# ATTiny5.net
KiCad netlist of a schematic drawn in EAGLE
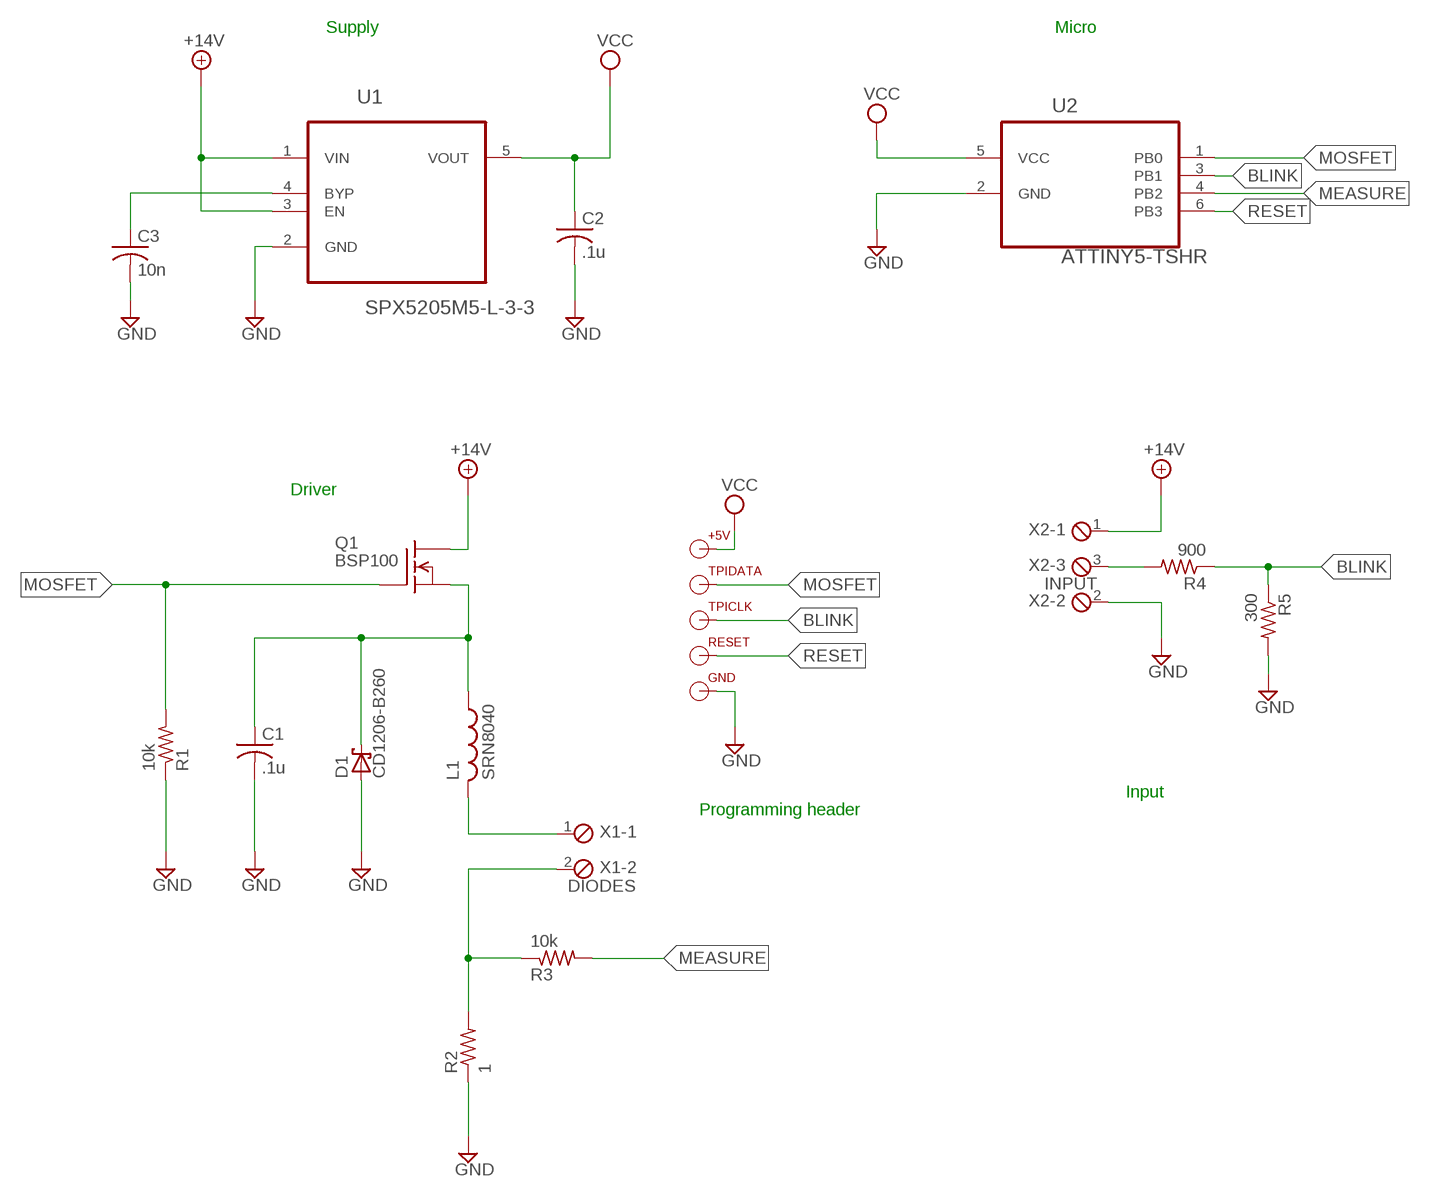
[diagram p0: schematic, sheet 1]

(export (version "E")
  (design (tool "Eeschema 10.0.6"))
  (components
    (comp (ref "+5V")
      (value "TPI")
      (footprint "eagle-import:TPI_PAD")
      (libsource (lib "eagle-import") (part "TPI"))
    )
    (comp (ref "C1")
      (value ".1u")
      (footprint "eagle-import:C0805")
      (libsource (lib "eagle-import") (part "C-USC0805"))
    )
    (comp (ref "C2")
      (value ".1u")
      (footprint "eagle-import:C0805")
      (libsource (lib "eagle-import") (part "C-USC0805"))
    )
    (comp (ref "C3")
      (value "10n")
      (footprint "eagle-import:C0603")
      (libsource (lib "eagle-import") (part "C-USC0603"))
    )
    (comp (ref "D1")
      (value "CD1206-B260")
      (footprint "eagle-import:D1206")
      (libsource (lib "eagle-import") (part "CD1206-B260"))
    )
    (comp (ref "GND")
      (value "TPI")
      (footprint "eagle-import:TPI_PAD")
      (libsource (lib "eagle-import") (part "TPI"))
    )
    (comp (ref "L1")
      (value "SRN8040")
      (footprint "eagle-import:SRN8040")
      (libsource (lib "eagle-import") (part "SRN8040"))
    )
    (comp (ref "Q1")
      (value "BSP100")
      (footprint "eagle-import:SOT223")
      (libsource (lib "eagle-import") (part "BSP100"))
    )
    (comp (ref "R1")
      (value "10k")
      (footprint "eagle-import:R1206")
      (libsource (lib "eagle-import") (part "R-US_R1206"))
    )
    (comp (ref "R2")
      (value "1")
      (footprint "eagle-import:R1206")
      (libsource (lib "eagle-import") (part "R-US_R1206"))
    )
    (comp (ref "R3")
      (value "10k")
      (footprint "eagle-import:R1206")
      (libsource (lib "eagle-import") (part "R-US_R1206"))
    )
    (comp (ref "R4")
      (value "900")
      (footprint "eagle-import:R1206")
      (libsource (lib "eagle-import") (part "R-US_R1206"))
    )
    (comp (ref "R5")
      (value "300")
      (footprint "eagle-import:R1206")
      (libsource (lib "eagle-import") (part "R-US_R1206"))
    )
    (comp (ref "RESET")
      (value "TPI")
      (footprint "eagle-import:TPI_PAD")
      (libsource (lib "eagle-import") (part "TPI"))
    )
    (comp (ref "TPICLK")
      (value "TPI")
      (footprint "eagle-import:TPI_PAD")
      (libsource (lib "eagle-import") (part "TPI"))
    )
    (comp (ref "TPIDATA")
      (value "TPI")
      (footprint "eagle-import:TPI_PAD")
      (libsource (lib "eagle-import") (part "TPI"))
    )
    (comp (ref "U1")
      (value "SPX5205M5-L-3-3")
      (footprint "eagle-import:SOT95P280X145-5N")
      (libsource (lib "eagle-import") (part "SPX5205M5-L-3-3"))
    )
    (comp (ref "U2")
      (value "ATTINY5-TSHR")
      (footprint "eagle-import:SOT95P280X145-6N")
      (libsource (lib "eagle-import") (part "ATTINY5-TSHR"))
    )
    (comp (ref "X1")
      (value "DIODES")
      (footprint "eagle-import:2POL254")
      (libsource (lib "eagle-import") (part "MPT2"))
    )
    (comp (ref "X2")
      (value "INPUT")
      (footprint "eagle-import:3POL254")
      (libsource (lib "eagle-import") (part "MPT3"))
    )
  )
  (nets
    (net (code "1") (name "+14V") (class "Default")
      (node (ref "Q1") (pin "2") (pinfunction "D_2") (pintype "passive"))
      (node (ref "Q1") (pin "TAB") (pinfunction "D_TAB") (pintype "passive"))
      (node (ref "U1") (pin "1") (pinfunction "VIN_1") (pintype "power_in"))
      (node (ref "U1") (pin "3") (pinfunction "EN_3") (pintype "input"))
      (node (ref "X2") (pin "1") (pinfunction "1_1") (pintype "passive"))
    )
    (net (code "2") (name "BLINK") (class "Default")
      (node (ref "R4") (pin "1") (pinfunction "1_1") (pintype "passive"))
      (node (ref "R5") (pin "1") (pinfunction "1_1") (pintype "passive"))
      (node (ref "TPICLK") (pin "P$1") (pinfunction "TPI_PIN_P$1") (pintype "bidirectional"))
      (node (ref "U2") (pin "3") (pinfunction "PB1_3") (pintype "bidirectional"))
    )
    (net (code "3") (name "GND") (class "Default")
      (node (ref "C1") (pin "2") (pinfunction "2_2") (pintype "passive"))
      (node (ref "C2") (pin "2") (pinfunction "2_2") (pintype "passive"))
      (node (ref "C3") (pin "2") (pinfunction "2_2") (pintype "passive"))
      (node (ref "D1") (pin "2") (pinfunction "A_2") (pintype "passive"))
      (node (ref "GND") (pin "P$1") (pinfunction "TPI_PIN_P$1") (pintype "bidirectional"))
      (node (ref "R1") (pin "1") (pinfunction "1_1") (pintype "passive"))
      (node (ref "R2") (pin "1") (pinfunction "1_1") (pintype "passive"))
      (node (ref "R5") (pin "2") (pinfunction "2_2") (pintype "passive"))
      (node (ref "U1") (pin "2") (pinfunction "GND_2") (pintype "passive"))
      (node (ref "U2") (pin "2") (pinfunction "GND_2") (pintype "passive"))
      (node (ref "X2") (pin "2") (pinfunction "1_2") (pintype "passive"))
    )
    (net (code "4") (name "MEASURE") (class "Default")
      (node (ref "R3") (pin "2") (pinfunction "2_2") (pintype "passive"))
      (node (ref "U2") (pin "4") (pinfunction "PB2_4") (pintype "bidirectional"))
    )
    (net (code "5") (name "MOSFET") (class "Default")
      (node (ref "Q1") (pin "1") (pinfunction "G_1") (pintype "passive"))
      (node (ref "R1") (pin "2") (pinfunction "2_2") (pintype "passive"))
      (node (ref "TPIDATA") (pin "P$1") (pinfunction "TPI_PIN_P$1") (pintype "bidirectional"))
      (node (ref "U2") (pin "1") (pinfunction "PB0_1") (pintype "bidirectional"))
    )
    (net (code "6") (name "Net-(D1-C)") (class "Default")
      (node (ref "C1") (pin "1") (pinfunction "1_1") (pintype "passive"))
      (node (ref "D1") (pin "1") (pinfunction "C_1") (pintype "passive"))
      (node (ref "L1") (pin "P$1") (pinfunction "1_P$1") (pintype "passive"))
      (node (ref "Q1") (pin "3") (pinfunction "S_3") (pintype "passive"))
    )
    (net (code "7") (name "Net-(L1-2)") (class "Default")
      (node (ref "L1") (pin "P$2") (pinfunction "2_P$2") (pintype "passive"))
      (node (ref "X1") (pin "1") (pinfunction "1_1") (pintype "passive"))
    )
    (net (code "8") (name "Net-(U1-BYP)") (class "Default")
      (node (ref "C3") (pin "1") (pinfunction "1_1") (pintype "passive"))
      (node (ref "U1") (pin "4") (pinfunction "BYP_4") (pintype "input"))
    )
    (net (code "9") (name "Net-(X1B-1)") (class "Default")
      (node (ref "R2") (pin "2") (pinfunction "2_2") (pintype "passive"))
      (node (ref "R3") (pin "1") (pinfunction "1_1") (pintype "passive"))
      (node (ref "X1") (pin "2") (pinfunction "1_2") (pintype "passive"))
    )
    (net (code "10") (name "Net-(X2C-1)") (class "Default")
      (node (ref "R4") (pin "2") (pinfunction "2_2") (pintype "passive"))
      (node (ref "X2") (pin "3") (pinfunction "1_3") (pintype "passive"))
    )
    (net (code "11") (name "RESET") (class "Default")
      (node (ref "RESET") (pin "P$1") (pinfunction "TPI_PIN_P$1") (pintype "bidirectional"))
      (node (ref "U2") (pin "6") (pinfunction "PB3_6") (pintype "bidirectional"))
    )
    (net (code "12") (name "VCC") (class "Default")
      (node (ref "+5V") (pin "P$1") (pinfunction "TPI_PIN_P$1") (pintype "bidirectional"))
      (node (ref "C2") (pin "1") (pinfunction "1_1") (pintype "passive"))
      (node (ref "U1") (pin "5") (pinfunction "VOUT_5") (pintype "output"))
      (node (ref "U2") (pin "5") (pinfunction "VCC_5") (pintype "power_in"))
    )
  )
)
